# rotometer.net
KiCad netlist of a schematic drawn in EAGLE
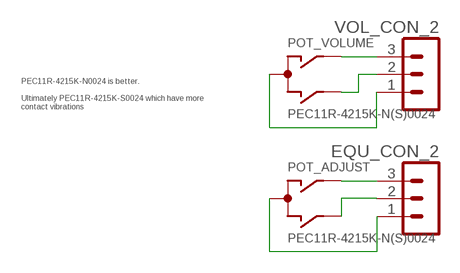
[diagram p0: schematic, sheet 1]

(export (version "E")
  (design (tool "Eeschema 10.0.6"))
  (components
    (comp (ref "EQU_CON_2")
      (value "MA03-1")
      (footprint "eagle-import:MA03-1")
      (libsource (lib "eagle-import") (part "MA03-1"))
    )
    (comp (ref "POT_ADJUST")
      (value "PEC11R-4215K-N(S)0024")
      (footprint "eagle-import:ALPS_EC12E_SW")
      (fields (field (name "MPN") "EC12E2424407"))
      (libsource (lib "eagle-import") (part "EC12E_SW"))
    )
    (comp (ref "POT_VOLUME")
      (value "PEC11R-4215K-N(S)0024")
      (footprint "eagle-import:ALPS_EC12E_SW")
      (fields (field (name "MPN") "EC12E2424407"))
      (libsource (lib "eagle-import") (part "EC12E_SW"))
    )
    (comp (ref "VOL_CON_2")
      (value "MA03-1")
      (footprint "eagle-import:MA03-1")
      (libsource (lib "eagle-import") (part "MA03-1"))
    )
  )
  (nets
    (net (code "1") (name "Net-(EQU_CON_2-Pad1)") (class "Default")
      (node (ref "EQU_CON_2") (pin "1") (pinfunction "1_1") (pintype "passive"))
      (node (ref "POT_ADJUST") (pin "C") (pinfunction "C_C") (pintype "passive"))
    )
    (net (code "2") (name "Net-(EQU_CON_2-Pad2)") (class "Default")
      (node (ref "EQU_CON_2") (pin "2") (pinfunction "2_2") (pintype "passive"))
      (node (ref "POT_ADJUST") (pin "B") (pinfunction "B_B") (pintype "passive"))
    )
    (net (code "3") (name "Net-(EQU_CON_2-Pad3)") (class "Default")
      (node (ref "EQU_CON_2") (pin "3") (pinfunction "3_3") (pintype "passive"))
      (node (ref "POT_ADJUST") (pin "A") (pinfunction "A_A") (pintype "passive"))
    )
    (net (code "4") (name "Net-(POT_VOLUME-PadA)") (class "Default")
      (node (ref "POT_VOLUME") (pin "A") (pinfunction "A_A") (pintype "passive"))
      (node (ref "VOL_CON_2") (pin "3") (pinfunction "3_3") (pintype "passive"))
    )
    (net (code "5") (name "Net-(POT_VOLUME-PadB)") (class "Default")
      (node (ref "POT_VOLUME") (pin "B") (pinfunction "B_B") (pintype "passive"))
      (node (ref "VOL_CON_2") (pin "2") (pinfunction "2_2") (pintype "passive"))
    )
    (net (code "6") (name "Net-(POT_VOLUME-PadC)") (class "Default")
      (node (ref "POT_VOLUME") (pin "C") (pinfunction "C_C") (pintype "passive"))
      (node (ref "VOL_CON_2") (pin "1") (pinfunction "1_1") (pintype "passive"))
    )
  )
)
